# MCU.net
KiCad netlist of a schematic drawn in Altium Designer
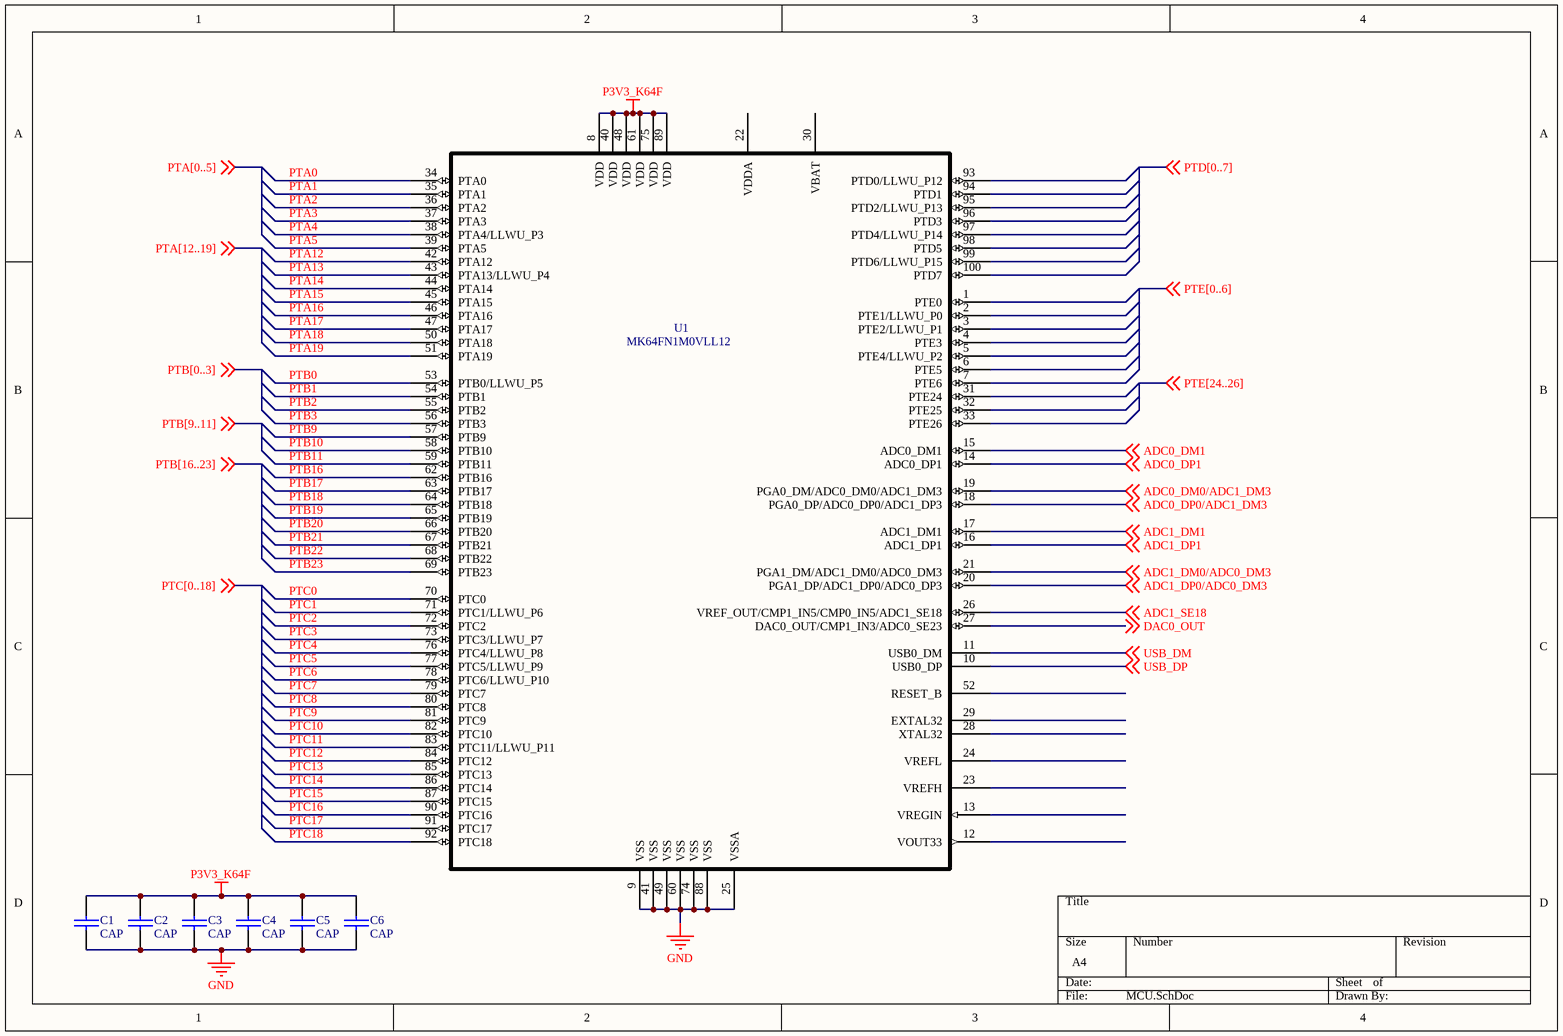
[diagram p0: MCU.SchDoc]

(export (version "E")
  (design (tool "Eeschema 10.0.6"))
  (components
    (comp (ref "C1") (value "CAP") (footprint "0805") (libsource (lib "LIBEBAL") (part "CAP")))
    (comp (ref "C2") (value "CAP") (footprint "0805") (libsource (lib "LIBEBAL") (part "CAP")))
    (comp (ref "C3") (value "CAP") (footprint "0805") (libsource (lib "LIBEBAL") (part "CAP")))
    (comp (ref "C4") (value "CAP") (footprint "0805") (libsource (lib "LIBEBAL") (part "CAP")))
    (comp (ref "C5") (value "CAP") (footprint "0805") (libsource (lib "LIBEBAL") (part "CAP")))
    (comp (ref "C6") (value "CAP") (footprint "0805") (libsource (lib "LIBEBAL") (part "CAP")))
    (comp (ref "U1")
      (value "MK64FN1M0VLL12")
      (footprint "LQFP-100_14X14X1")
      (description "Imported")
      (fields (field (name "MANUFACTURER_PART_NUMBER") "mk64fn1m0vll12"))
      (libsource (lib "MK64FN1M0VLL12") (part "MK64FN1M0VLL12"))
    )
  )
  (nets
    (net (code "1") (name "ADC0_DM0{slash}ADC1_DM3") (class "Default")
      (node (ref "U1") (pin "19") (pinfunction "PGA0_DM/ADC0_DM0/ADC1_DM3_19") (pintype "bidirectional"))
    )
    (net (code "2") (name "ADC0_DM1") (class "Default")
      (node (ref "U1") (pin "15") (pinfunction "ADC0_DM1_15") (pintype "bidirectional"))
    )
    (net (code "3") (name "ADC0_DP0{slash}ADC1_DM3") (class "Default")
      (node (ref "U1") (pin "18") (pinfunction "PGA0_DP/ADC0_DP0/ADC1_DP3_18") (pintype "bidirectional"))
    )
    (net (code "4") (name "ADC0_DP1") (class "Default")
      (node (ref "U1") (pin "14") (pinfunction "ADC0_DP1_14") (pintype "bidirectional"))
    )
    (net (code "5") (name "ADC1_DM0{slash}ADC0_DM3") (class "Default")
      (node (ref "U1") (pin "21") (pinfunction "PGA1_DM/ADC1_DM0/ADC0_DM3_21") (pintype "bidirectional"))
    )
    (net (code "6") (name "ADC1_DM1") (class "Default")
      (node (ref "U1") (pin "17") (pinfunction "ADC1_DM1_17") (pintype "bidirectional"))
    )
    (net (code "7") (name "ADC1_DP0{slash}ADC0_DM3") (class "Default")
      (node (ref "U1") (pin "20") (pinfunction "PGA1_DP/ADC1_DP0/ADC0_DP3_20") (pintype "bidirectional"))
    )
    (net (code "8") (name "ADC1_DP1") (class "Default")
      (node (ref "U1") (pin "16") (pinfunction "ADC1_DP1_16") (pintype "bidirectional"))
    )
    (net (code "9") (name "ADC1_SE18") (class "Default")
      (node (ref "U1") (pin "26") (pinfunction "VREF_OUT/CMP1_IN5/CMP0_IN5/ADC1_SE18_26") (pintype "bidirectional"))
    )
    (net (code "10") (name "DAC0_OUT") (class "Default")
      (node (ref "U1") (pin "27") (pinfunction "DAC0_OUT/CMP1_IN3/ADC0_SE23_27") (pintype "bidirectional"))
    )
    (net (code "11") (name "GND") (class "Default")
      (node (ref "C1") (pin "2") (pinfunction "2_2") (pintype "passive"))
      (node (ref "C2") (pin "2") (pinfunction "2_2") (pintype "passive"))
      (node (ref "C3") (pin "2") (pinfunction "2_2") (pintype "passive"))
      (node (ref "C4") (pin "2") (pinfunction "2_2") (pintype "passive"))
      (node (ref "C5") (pin "2") (pinfunction "2_2") (pintype "passive"))
      (node (ref "C6") (pin "2") (pinfunction "2_2") (pintype "passive"))
      (node (ref "U1") (pin "25") (pinfunction "VSSA_25") (pintype "power_in"))
      (node (ref "U1") (pin "41") (pinfunction "VSS_41") (pintype "power_in"))
      (node (ref "U1") (pin "49") (pinfunction "VSS_49") (pintype "power_in"))
      (node (ref "U1") (pin "60") (pinfunction "VSS_60") (pintype "power_in"))
      (node (ref "U1") (pin "74") (pinfunction "VSS_74") (pintype "power_in"))
      (node (ref "U1") (pin "88") (pinfunction "VSS_88") (pintype "power_in"))
      (node (ref "U1") (pin "9") (pinfunction "VSS_9") (pintype "power_in"))
    )
    (net (code "12") (name "P3V3_K64F") (class "Default")
      (node (ref "C1") (pin "1") (pinfunction "1_1") (pintype "passive"))
      (node (ref "C2") (pin "1") (pinfunction "1_1") (pintype "passive"))
      (node (ref "C3") (pin "1") (pinfunction "1_1") (pintype "passive"))
      (node (ref "C4") (pin "1") (pinfunction "1_1") (pintype "passive"))
      (node (ref "C5") (pin "1") (pinfunction "1_1") (pintype "passive"))
      (node (ref "C6") (pin "1") (pinfunction "1_1") (pintype "passive"))
      (node (ref "U1") (pin "40") (pinfunction "VDD_40") (pintype "power_in"))
      (node (ref "U1") (pin "48") (pinfunction "VDD_48") (pintype "power_in"))
      (node (ref "U1") (pin "61") (pinfunction "VDD_61") (pintype "power_in"))
      (node (ref "U1") (pin "75") (pinfunction "VDD_75") (pintype "power_in"))
      (node (ref "U1") (pin "8") (pinfunction "VDD_8") (pintype "power_in"))
      (node (ref "U1") (pin "89") (pinfunction "VDD_89") (pintype "power_in"))
    )
    (net (code "13") (name "PTA0") (class "Default")
      (node (ref "U1") (pin "34") (pinfunction "PTA0_34") (pintype "bidirectional"))
    )
    (net (code "14") (name "PTA1") (class "Default")
      (node (ref "U1") (pin "35") (pinfunction "PTA1_35") (pintype "bidirectional"))
    )
    (net (code "15") (name "PTA2") (class "Default")
      (node (ref "U1") (pin "36") (pinfunction "PTA2_36") (pintype "bidirectional"))
    )
    (net (code "16") (name "PTA3") (class "Default")
      (node (ref "U1") (pin "37") (pinfunction "PTA3_37") (pintype "bidirectional"))
    )
    (net (code "17") (name "PTA4") (class "Default")
      (node (ref "U1") (pin "38") (pinfunction "PTA4/LLWU_P3_38") (pintype "bidirectional"))
    )
    (net (code "18") (name "PTA5") (class "Default")
      (node (ref "U1") (pin "39") (pinfunction "PTA5_39") (pintype "bidirectional"))
    )
    (net (code "19") (name "PTA12") (class "Default")
      (node (ref "U1") (pin "42") (pinfunction "PTA12_42") (pintype "bidirectional"))
    )
    (net (code "20") (name "PTA13") (class "Default")
      (node (ref "U1") (pin "43") (pinfunction "PTA13/LLWU_P4_43") (pintype "bidirectional"))
    )
    (net (code "21") (name "PTA14") (class "Default")
      (node (ref "U1") (pin "44") (pinfunction "PTA14_44") (pintype "bidirectional"))
    )
    (net (code "22") (name "PTA15") (class "Default")
      (node (ref "U1") (pin "45") (pinfunction "PTA15_45") (pintype "bidirectional"))
    )
    (net (code "23") (name "PTA16") (class "Default")
      (node (ref "U1") (pin "46") (pinfunction "PTA16_46") (pintype "bidirectional"))
    )
    (net (code "24") (name "PTA17") (class "Default")
      (node (ref "U1") (pin "47") (pinfunction "PTA17_47") (pintype "bidirectional"))
    )
    (net (code "25") (name "PTA18") (class "Default")
      (node (ref "U1") (pin "50") (pinfunction "PTA18_50") (pintype "bidirectional"))
    )
    (net (code "26") (name "PTA19") (class "Default")
      (node (ref "U1") (pin "51") (pinfunction "PTA19_51") (pintype "bidirectional"))
    )
    (net (code "29") (name "PTB0") (class "Default")
      (node (ref "U1") (pin "53") (pinfunction "PTB0/LLWU_P5_53") (pintype "bidirectional"))
    )
    (net (code "30") (name "PTB1") (class "Default")
      (node (ref "U1") (pin "54") (pinfunction "PTB1_54") (pintype "bidirectional"))
    )
    (net (code "31") (name "PTB2") (class "Default")
      (node (ref "U1") (pin "55") (pinfunction "PTB2_55") (pintype "bidirectional"))
    )
    (net (code "32") (name "PTB3") (class "Default")
      (node (ref "U1") (pin "56") (pinfunction "PTB3_56") (pintype "bidirectional"))
    )
    (net (code "33") (name "PTB9") (class "Default")
      (node (ref "U1") (pin "57") (pinfunction "PTB9_57") (pintype "bidirectional"))
    )
    (net (code "34") (name "PTB10") (class "Default")
      (node (ref "U1") (pin "58") (pinfunction "PTB10_58") (pintype "bidirectional"))
    )
    (net (code "35") (name "PTB11") (class "Default")
      (node (ref "U1") (pin "59") (pinfunction "PTB11_59") (pintype "bidirectional"))
    )
    (net (code "36") (name "PTB16") (class "Default")
      (node (ref "U1") (pin "62") (pinfunction "PTB16_62") (pintype "bidirectional"))
    )
    (net (code "37") (name "PTB17") (class "Default")
      (node (ref "U1") (pin "63") (pinfunction "PTB17_63") (pintype "bidirectional"))
    )
    (net (code "38") (name "PTB18") (class "Default")
      (node (ref "U1") (pin "64") (pinfunction "PTB18_64") (pintype "bidirectional"))
    )
    (net (code "39") (name "PTB19") (class "Default")
      (node (ref "U1") (pin "65") (pinfunction "PTB19_65") (pintype "bidirectional"))
    )
    (net (code "40") (name "PTB20") (class "Default")
      (node (ref "U1") (pin "66") (pinfunction "PTB20_66") (pintype "bidirectional"))
    )
    (net (code "41") (name "PTB21") (class "Default")
      (node (ref "U1") (pin "67") (pinfunction "PTB21_67") (pintype "bidirectional"))
    )
    (net (code "42") (name "PTB22") (class "Default")
      (node (ref "U1") (pin "68") (pinfunction "PTB22_68") (pintype "bidirectional"))
    )
    (net (code "43") (name "PTB23") (class "Default")
      (node (ref "U1") (pin "69") (pinfunction "PTB23_69") (pintype "bidirectional"))
    )
    (net (code "47") (name "PTC0") (class "Default")
      (node (ref "U1") (pin "70") (pinfunction "PTC0_70") (pintype "bidirectional"))
    )
    (net (code "48") (name "PTC1") (class "Default")
      (node (ref "U1") (pin "71") (pinfunction "PTC1/LLWU_P6_71") (pintype "bidirectional"))
    )
    (net (code "49") (name "PTC2") (class "Default")
      (node (ref "U1") (pin "72") (pinfunction "PTC2_72") (pintype "bidirectional"))
    )
    (net (code "50") (name "PTC3") (class "Default")
      (node (ref "U1") (pin "73") (pinfunction "PTC3/LLWU_P7_73") (pintype "bidirectional"))
    )
    (net (code "51") (name "PTC4") (class "Default")
      (node (ref "U1") (pin "76") (pinfunction "PTC4/LLWU_P8_76") (pintype "bidirectional"))
    )
    (net (code "52") (name "PTC5") (class "Default")
      (node (ref "U1") (pin "77") (pinfunction "PTC5/LLWU_P9_77") (pintype "bidirectional"))
    )
    (net (code "53") (name "PTC6") (class "Default")
      (node (ref "U1") (pin "78") (pinfunction "PTC6/LLWU_P10_78") (pintype "bidirectional"))
    )
    (net (code "54") (name "PTC7") (class "Default")
      (node (ref "U1") (pin "79") (pinfunction "PTC7_79") (pintype "bidirectional"))
    )
    (net (code "55") (name "PTC8") (class "Default")
      (node (ref "U1") (pin "80") (pinfunction "PTC8_80") (pintype "bidirectional"))
    )
    (net (code "56") (name "PTC9") (class "Default")
      (node (ref "U1") (pin "81") (pinfunction "PTC9_81") (pintype "bidirectional"))
    )
    (net (code "57") (name "PTC10") (class "Default")
      (node (ref "U1") (pin "82") (pinfunction "PTC10_82") (pintype "bidirectional"))
    )
    (net (code "58") (name "PTC11") (class "Default")
      (node (ref "U1") (pin "83") (pinfunction "PTC11/LLWU_P11_83") (pintype "bidirectional"))
    )
    (net (code "59") (name "PTC12") (class "Default")
      (node (ref "U1") (pin "84") (pinfunction "PTC12_84") (pintype "bidirectional"))
    )
    (net (code "60") (name "PTC13") (class "Default")
      (node (ref "U1") (pin "85") (pinfunction "PTC13_85") (pintype "bidirectional"))
    )
    (net (code "61") (name "PTC14") (class "Default")
      (node (ref "U1") (pin "86") (pinfunction "PTC14_86") (pintype "bidirectional"))
    )
    (net (code "62") (name "PTC15") (class "Default")
      (node (ref "U1") (pin "87") (pinfunction "PTC15_87") (pintype "bidirectional"))
    )
    (net (code "63") (name "PTC16") (class "Default")
      (node (ref "U1") (pin "90") (pinfunction "PTC16_90") (pintype "bidirectional"))
    )
    (net (code "64") (name "PTC17") (class "Default")
      (node (ref "U1") (pin "91") (pinfunction "PTC17_91") (pintype "bidirectional"))
    )
    (net (code "65") (name "PTC18") (class "Default")
      (node (ref "U1") (pin "92") (pinfunction "PTC18_92") (pintype "bidirectional"))
    )
    (net (code "70") (name "USB_DM") (class "Default")
      (node (ref "U1") (pin "11") (pinfunction "USB0_DM_11") (pintype "passive"))
    )
    (net (code "71") (name "USB_DP") (class "Default")
      (node (ref "U1") (pin "10") (pinfunction "USB0_DP_10") (pintype "passive"))
    )
    (net (code "72") (name "unconnected-(U1-EXTAL32-Pad29)") (class "Default")
      (node (ref "U1") (pin "29") (pinfunction "EXTAL32_29") (pintype "passive"))
    )
    (net (code "73") (name "unconnected-(U1-PTD0{slash}LLWU_P12-Pad93)") (class "Default")
      (node (ref "U1") (pin "93") (pinfunction "PTD0/LLWU_P12_93") (pintype "bidirectional"))
    )
    (net (code "74") (name "unconnected-(U1-PTD1-Pad94)") (class "Default")
      (node (ref "U1") (pin "94") (pinfunction "PTD1_94") (pintype "bidirectional"))
    )
    (net (code "75") (name "unconnected-(U1-PTD2{slash}LLWU_P13-Pad95)") (class "Default")
      (node (ref "U1") (pin "95") (pinfunction "PTD2/LLWU_P13_95") (pintype "bidirectional"))
    )
    (net (code "76") (name "unconnected-(U1-PTD3-Pad96)") (class "Default")
      (node (ref "U1") (pin "96") (pinfunction "PTD3_96") (pintype "bidirectional"))
    )
    (net (code "77") (name "unconnected-(U1-PTD4{slash}LLWU_P14-Pad97)") (class "Default")
      (node (ref "U1") (pin "97") (pinfunction "PTD4/LLWU_P14_97") (pintype "bidirectional"))
    )
    (net (code "78") (name "unconnected-(U1-PTD5-Pad98)") (class "Default")
      (node (ref "U1") (pin "98") (pinfunction "PTD5_98") (pintype "bidirectional"))
    )
    (net (code "79") (name "unconnected-(U1-PTD6{slash}LLWU_P15-Pad99)") (class "Default")
      (node (ref "U1") (pin "99") (pinfunction "PTD6/LLWU_P15_99") (pintype "bidirectional"))
    )
    (net (code "80") (name "unconnected-(U1-PTD7-Pad100)") (class "Default")
      (node (ref "U1") (pin "100") (pinfunction "PTD7_100") (pintype "bidirectional"))
    )
    (net (code "81") (name "unconnected-(U1-PTE0-Pad1)") (class "Default")
      (node (ref "U1") (pin "1") (pinfunction "PTE0_1") (pintype "bidirectional"))
    )
    (net (code "82") (name "unconnected-(U1-PTE1{slash}LLWU_P0-Pad2)") (class "Default")
      (node (ref "U1") (pin "2") (pinfunction "PTE1/LLWU_P0_2") (pintype "bidirectional"))
    )
    (net (code "83") (name "unconnected-(U1-PTE2{slash}LLWU_P1-Pad3)") (class "Default")
      (node (ref "U1") (pin "3") (pinfunction "PTE2/LLWU_P1_3") (pintype "bidirectional"))
    )
    (net (code "84") (name "unconnected-(U1-PTE3-Pad4)") (class "Default")
      (node (ref "U1") (pin "4") (pinfunction "PTE3_4") (pintype "bidirectional"))
    )
    (net (code "85") (name "unconnected-(U1-PTE4{slash}LLWU_P2-Pad5)") (class "Default")
      (node (ref "U1") (pin "5") (pinfunction "PTE4/LLWU_P2_5") (pintype "bidirectional"))
    )
    (net (code "86") (name "unconnected-(U1-PTE5-Pad6)") (class "Default")
      (node (ref "U1") (pin "6") (pinfunction "PTE5_6") (pintype "bidirectional"))
    )
    (net (code "87") (name "unconnected-(U1-PTE6-Pad7)") (class "Default")
      (node (ref "U1") (pin "7") (pinfunction "PTE6_7") (pintype "bidirectional"))
    )
    (net (code "88") (name "unconnected-(U1-PTE24-Pad31)") (class "Default")
      (node (ref "U1") (pin "31") (pinfunction "PTE24_31") (pintype "bidirectional"))
    )
    (net (code "89") (name "unconnected-(U1-PTE25-Pad32)") (class "Default")
      (node (ref "U1") (pin "32") (pinfunction "PTE25_32") (pintype "bidirectional"))
    )
    (net (code "90") (name "unconnected-(U1-PTE26-Pad33)") (class "Default")
      (node (ref "U1") (pin "33") (pinfunction "PTE26_33") (pintype "bidirectional"))
    )
    (net (code "91") (name "unconnected-(U1-RESET_B-Pad52)") (class "Default")
      (node (ref "U1") (pin "52") (pinfunction "RESET_B_52") (pintype "passive"))
    )
    (net (code "92") (name "unconnected-(U1-VBAT-Pad30)") (class "Default")
      (node (ref "U1") (pin "30") (pinfunction "VBAT_30") (pintype "power_in"))
    )
    (net (code "93") (name "unconnected-(U1-VDDA-Pad22)") (class "Default")
      (node (ref "U1") (pin "22") (pinfunction "VDDA_22") (pintype "power_in"))
    )
    (net (code "94") (name "unconnected-(U1-VOUT33-Pad12)") (class "Default")
      (node (ref "U1") (pin "12") (pinfunction "VOUT33_12") (pintype "output"))
    )
    (net (code "95") (name "unconnected-(U1-VREFH-Pad23)") (class "Default")
      (node (ref "U1") (pin "23") (pinfunction "VREFH_23") (pintype "power_in"))
    )
    (net (code "96") (name "unconnected-(U1-VREFL-Pad24)") (class "Default")
      (node (ref "U1") (pin "24") (pinfunction "VREFL_24") (pintype "power_in"))
    )
    (net (code "97") (name "unconnected-(U1-VREGIN-Pad13)") (class "Default")
      (node (ref "U1") (pin "13") (pinfunction "VREGIN_13") (pintype "input"))
    )
    (net (code "98") (name "unconnected-(U1-XTAL32-Pad28)") (class "Default")
      (node (ref "U1") (pin "28") (pinfunction "XTAL32_28") (pintype "passive"))
    )
  )
)
